# atmega128ictop.net
KiCad netlist of a schematic drawn in EAGLE
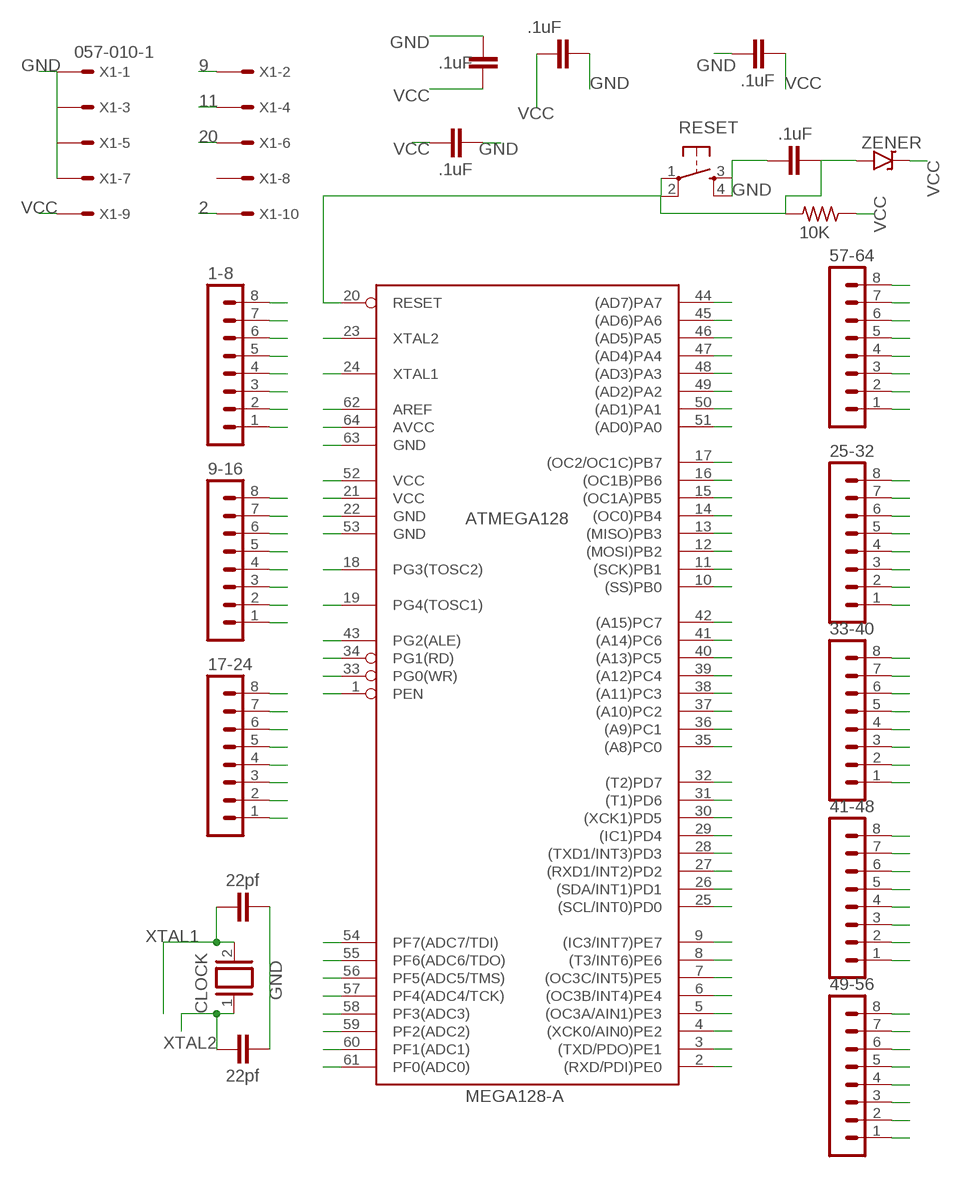
[diagram p0: schematic, sheet 1]

(export (version "E")
  (design (tool "Eeschema 10.0.6"))
  (components
    (comp (ref "1-8")
      (value "MA08-1")
      (footprint "eagle-import:MA08-1")
      (libsource (lib "eagle-import") (part "MA08-1"))
    )
    (comp (ref "9-16")
      (value "MA08-1")
      (footprint "eagle-import:MA08-1")
      (libsource (lib "eagle-import") (part "MA08-1"))
    )
    (comp (ref "17-24")
      (value "MA08-1")
      (footprint "eagle-import:MA08-1")
      (libsource (lib "eagle-import") (part "MA08-1"))
    )
    (comp (ref "25-32")
      (value "MA08-1")
      (footprint "eagle-import:MA08-1")
      (libsource (lib "eagle-import") (part "MA08-1"))
    )
    (comp (ref "33-40")
      (value "MA08-1")
      (footprint "eagle-import:MA08-1")
      (libsource (lib "eagle-import") (part "MA08-1"))
    )
    (comp (ref "41-48")
      (value "MA08-1")
      (footprint "eagle-import:MA08-1")
      (libsource (lib "eagle-import") (part "MA08-1"))
    )
    (comp (ref "49-56")
      (value "MA08-1")
      (footprint "eagle-import:MA08-1")
      (libsource (lib "eagle-import") (part "MA08-1"))
    )
    (comp (ref "57-64")
      (value "MA08-1")
      (footprint "eagle-import:MA08-1")
      (libsource (lib "eagle-import") (part "MA08-1"))
    )
    (comp (ref "ATMEGA128")
      (value "MEGA128-A")
      (footprint "eagle-import:TQFP64")
      (fields (field (name "MPN") "ATMEGA128-16AU"))
      (libsource (lib "eagle-import") (part "MEGA128-A"))
    )
    (comp (ref "C1")
      (value ".1uF")
      (footprint "eagle-import:C5B2.5")
      (libsource (lib "eagle-import") (part "C5/2.5"))
    )
    (comp (ref "C2")
      (value ".1uF")
      (footprint "eagle-import:C5B2.5")
      (libsource (lib "eagle-import") (part "C5/2.5"))
    )
    (comp (ref "C3")
      (value "22pf")
      (footprint "eagle-import:C5B2.5")
      (libsource (lib "eagle-import") (part "C5/2.5"))
    )
    (comp (ref "C4")
      (value "22pf")
      (footprint "eagle-import:C5B2.5")
      (libsource (lib "eagle-import") (part "C5/2.5"))
    )
    (comp (ref "C5")
      (value ".1uF")
      (footprint "eagle-import:C5B2.5")
      (libsource (lib "eagle-import") (part "C5/2.5"))
    )
    (comp (ref "C6")
      (value ".1uF")
      (footprint "eagle-import:C5B2.5")
      (libsource (lib "eagle-import") (part "C5/2.5"))
    )
    (comp (ref "C7")
      (value ".1uF")
      (footprint "eagle-import:C5B2.5")
      (libsource (lib "eagle-import") (part "C5/2.5"))
    )
    (comp (ref "CLOCK")
      (value "XTAL/S")
      (footprint "eagle-import:QS")
      (libsource (lib "eagle-import") (part "XTAL/S"))
    )
    (comp (ref "D1")
      (value "ZENER")
      (footprint "eagle-import:DO35-2")
      (libsource (lib "eagle-import") (part "1N9ZENER2"))
    )
    (comp (ref "R1")
      (value "10K")
      (footprint "eagle-import:0204_5")
      (libsource (lib "eagle-import") (part "R-US_0204/5"))
    )
    (comp (ref "RESET")
      (value "DTS-6")
      (footprint "eagle-import:DTS-6")
      (libsource (lib "eagle-import") (part "DTS-6"))
    )
    (comp (ref "X1")
      (value "057-010-1")
      (footprint "eagle-import:057-010-1")
      (libsource (lib "eagle-import") (part "057-010-1"))
    )
  )
  (nets
    (net (code "1") (name "/1") (class "Default")
      (node (ref "1-8") (pin "1") (pinfunction "1_1") (pintype "passive"))
      (node (ref "ATMEGA128") (pin "1") (pinfunction "PEN_1") (pintype "input"))
    )
    (net (code "2") (name "/2") (class "Default")
      (node (ref "1-8") (pin "2") (pinfunction "2_2") (pintype "passive"))
      (node (ref "ATMEGA128") (pin "2") (pinfunction "(RXD/PDI)PE0_2") (pintype "bidirectional"))
      (node (ref "X1") (pin "10") (pinfunction "S_10") (pintype "passive"))
    )
    (net (code "3") (name "/3") (class "Default")
      (node (ref "1-8") (pin "3") (pinfunction "3_3") (pintype "passive"))
      (node (ref "ATMEGA128") (pin "3") (pinfunction "(TXD/PDO)PE1_3") (pintype "bidirectional"))
    )
    (net (code "4") (name "/4") (class "Default")
      (node (ref "1-8") (pin "4") (pinfunction "4_4") (pintype "passive"))
      (node (ref "ATMEGA128") (pin "4") (pinfunction "(XCK0/AIN0)PE2_4") (pintype "bidirectional"))
    )
    (net (code "5") (name "/5") (class "Default")
      (node (ref "1-8") (pin "5") (pinfunction "5_5") (pintype "passive"))
      (node (ref "ATMEGA128") (pin "5") (pinfunction "(OC3A/AIN1)PE3_5") (pintype "bidirectional"))
    )
    (net (code "6") (name "/6") (class "Default")
      (node (ref "1-8") (pin "6") (pinfunction "6_6") (pintype "passive"))
      (node (ref "ATMEGA128") (pin "6") (pinfunction "(OC3B/INT4)PE4_6") (pintype "bidirectional"))
    )
    (net (code "7") (name "/7") (class "Default")
      (node (ref "1-8") (pin "7") (pinfunction "7_7") (pintype "passive"))
      (node (ref "ATMEGA128") (pin "7") (pinfunction "(OC3C/INT5)PE5_7") (pintype "bidirectional"))
    )
    (net (code "8") (name "/8") (class "Default")
      (node (ref "1-8") (pin "8") (pinfunction "8_8") (pintype "passive"))
      (node (ref "ATMEGA128") (pin "8") (pinfunction "(T3/INT6)PE6_8") (pintype "bidirectional"))
    )
    (net (code "9") (name "/9") (class "Default")
      (node (ref "9-16") (pin "1") (pinfunction "1_1") (pintype "passive"))
      (node (ref "ATMEGA128") (pin "9") (pinfunction "(IC3/INT7)PE7_9") (pintype "bidirectional"))
      (node (ref "X1") (pin "2") (pinfunction "S_2") (pintype "passive"))
    )
    (net (code "10") (name "/10") (class "Default")
      (node (ref "9-16") (pin "2") (pinfunction "2_2") (pintype "passive"))
      (node (ref "ATMEGA128") (pin "10") (pinfunction "(SS)PB0_10") (pintype "bidirectional"))
    )
    (net (code "11") (name "/11") (class "Default")
      (node (ref "9-16") (pin "3") (pinfunction "3_3") (pintype "passive"))
      (node (ref "ATMEGA128") (pin "11") (pinfunction "(SCK)PB1_11") (pintype "bidirectional"))
      (node (ref "X1") (pin "4") (pinfunction "S_4") (pintype "passive"))
    )
    (net (code "12") (name "/12") (class "Default")
      (node (ref "9-16") (pin "4") (pinfunction "4_4") (pintype "passive"))
      (node (ref "ATMEGA128") (pin "12") (pinfunction "(MOSI)PB2_12") (pintype "bidirectional"))
    )
    (net (code "13") (name "/13") (class "Default")
      (node (ref "9-16") (pin "5") (pinfunction "5_5") (pintype "passive"))
      (node (ref "ATMEGA128") (pin "13") (pinfunction "(MISO)PB3_13") (pintype "bidirectional"))
    )
    (net (code "14") (name "/14") (class "Default")
      (node (ref "9-16") (pin "6") (pinfunction "6_6") (pintype "passive"))
      (node (ref "ATMEGA128") (pin "14") (pinfunction "(OC0)PB4_14") (pintype "bidirectional"))
    )
    (net (code "15") (name "/15") (class "Default")
      (node (ref "9-16") (pin "7") (pinfunction "7_7") (pintype "passive"))
      (node (ref "ATMEGA128") (pin "15") (pinfunction "(OC1A)PB5_15") (pintype "bidirectional"))
    )
    (net (code "16") (name "/16") (class "Default")
      (node (ref "9-16") (pin "8") (pinfunction "8_8") (pintype "passive"))
      (node (ref "ATMEGA128") (pin "16") (pinfunction "(OC1B)PB6_16") (pintype "bidirectional"))
    )
    (net (code "17") (name "/17") (class "Default")
      (node (ref "17-24") (pin "1") (pinfunction "1_1") (pintype "passive"))
      (node (ref "ATMEGA128") (pin "17") (pinfunction "(OC2/OC1C)PB7_17") (pintype "bidirectional"))
    )
    (net (code "18") (name "/18") (class "Default")
      (node (ref "17-24") (pin "2") (pinfunction "2_2") (pintype "passive"))
      (node (ref "ATMEGA128") (pin "18") (pinfunction "PG3(TOSC2)_18") (pintype "bidirectional"))
    )
    (net (code "19") (name "/19") (class "Default")
      (node (ref "17-24") (pin "3") (pinfunction "3_3") (pintype "passive"))
      (node (ref "ATMEGA128") (pin "19") (pinfunction "PG4(TOSC1)_19") (pintype "bidirectional"))
    )
    (net (code "20") (name "/20") (class "Default")
      (node (ref "17-24") (pin "4") (pinfunction "4_4") (pintype "passive"))
      (node (ref "ATMEGA128") (pin "20") (pinfunction "RESET_20") (pintype "input"))
      (node (ref "C5") (pin "1") (pinfunction "1_1") (pintype "passive"))
      (node (ref "D1") (pin "A") (pinfunction "A_A") (pintype "passive"))
      (node (ref "R1") (pin "2") (pinfunction "2_2") (pintype "passive"))
      (node (ref "RESET") (pin "1") (pinfunction "1_1") (pintype "passive"))
      (node (ref "RESET") (pin "2") (pinfunction "2_2") (pintype "passive"))
      (node (ref "X1") (pin "6") (pinfunction "S_6") (pintype "passive"))
    )
    (net (code "21") (name "/25") (class "Default")
      (node (ref "25-32") (pin "1") (pinfunction "1_1") (pintype "passive"))
      (node (ref "ATMEGA128") (pin "25") (pinfunction "(SCL/INT0)PD0_25") (pintype "bidirectional"))
    )
    (net (code "22") (name "/26") (class "Default")
      (node (ref "25-32") (pin "2") (pinfunction "2_2") (pintype "passive"))
      (node (ref "ATMEGA128") (pin "26") (pinfunction "(SDA/INT1)PD1_26") (pintype "bidirectional"))
    )
    (net (code "23") (name "/27") (class "Default")
      (node (ref "25-32") (pin "3") (pinfunction "3_3") (pintype "passive"))
      (node (ref "ATMEGA128") (pin "27") (pinfunction "(RXD1/INT2)PD2_27") (pintype "bidirectional"))
    )
    (net (code "24") (name "/28") (class "Default")
      (node (ref "25-32") (pin "4") (pinfunction "4_4") (pintype "passive"))
      (node (ref "ATMEGA128") (pin "28") (pinfunction "(TXD1/INT3)PD3_28") (pintype "bidirectional"))
    )
    (net (code "25") (name "/29") (class "Default")
      (node (ref "25-32") (pin "5") (pinfunction "5_5") (pintype "passive"))
      (node (ref "ATMEGA128") (pin "29") (pinfunction "(IC1)PD4_29") (pintype "bidirectional"))
    )
    (net (code "26") (name "/30") (class "Default")
      (node (ref "25-32") (pin "6") (pinfunction "6_6") (pintype "passive"))
      (node (ref "ATMEGA128") (pin "30") (pinfunction "(XCK1)PD5_30") (pintype "bidirectional"))
    )
    (net (code "27") (name "/31") (class "Default")
      (node (ref "25-32") (pin "7") (pinfunction "7_7") (pintype "passive"))
      (node (ref "ATMEGA128") (pin "31") (pinfunction "(T1)PD6_31") (pintype "bidirectional"))
    )
    (net (code "28") (name "/32") (class "Default")
      (node (ref "25-32") (pin "8") (pinfunction "8_8") (pintype "passive"))
      (node (ref "ATMEGA128") (pin "32") (pinfunction "(T2)PD7_32") (pintype "bidirectional"))
    )
    (net (code "29") (name "/33") (class "Default")
      (node (ref "33-40") (pin "1") (pinfunction "1_1") (pintype "passive"))
      (node (ref "ATMEGA128") (pin "33") (pinfunction "PG0(WR)_33") (pintype "bidirectional"))
    )
    (net (code "30") (name "/34") (class "Default")
      (node (ref "33-40") (pin "2") (pinfunction "2_2") (pintype "passive"))
      (node (ref "ATMEGA128") (pin "34") (pinfunction "PG1(RD)_34") (pintype "bidirectional"))
    )
    (net (code "31") (name "/35") (class "Default")
      (node (ref "33-40") (pin "3") (pinfunction "3_3") (pintype "passive"))
      (node (ref "ATMEGA128") (pin "35") (pinfunction "(A8)PC0_35") (pintype "output"))
    )
    (net (code "32") (name "/36") (class "Default")
      (node (ref "33-40") (pin "4") (pinfunction "4_4") (pintype "passive"))
      (node (ref "ATMEGA128") (pin "36") (pinfunction "(A9)PC1_36") (pintype "output"))
    )
    (net (code "33") (name "/37") (class "Default")
      (node (ref "33-40") (pin "5") (pinfunction "5_5") (pintype "passive"))
      (node (ref "ATMEGA128") (pin "37") (pinfunction "(A10)PC2_37") (pintype "output"))
    )
    (net (code "34") (name "/38") (class "Default")
      (node (ref "33-40") (pin "6") (pinfunction "6_6") (pintype "passive"))
      (node (ref "ATMEGA128") (pin "38") (pinfunction "(A11)PC3_38") (pintype "output"))
    )
    (net (code "35") (name "/39") (class "Default")
      (node (ref "33-40") (pin "7") (pinfunction "7_7") (pintype "passive"))
      (node (ref "ATMEGA128") (pin "39") (pinfunction "(A12)PC4_39") (pintype "output"))
    )
    (net (code "36") (name "/40") (class "Default")
      (node (ref "33-40") (pin "8") (pinfunction "8_8") (pintype "passive"))
      (node (ref "ATMEGA128") (pin "40") (pinfunction "(A13)PC5_40") (pintype "output"))
    )
    (net (code "37") (name "/41") (class "Default")
      (node (ref "41-48") (pin "1") (pinfunction "1_1") (pintype "passive"))
      (node (ref "ATMEGA128") (pin "41") (pinfunction "(A14)PC6_41") (pintype "output"))
    )
    (net (code "38") (name "/42") (class "Default")
      (node (ref "41-48") (pin "2") (pinfunction "2_2") (pintype "passive"))
      (node (ref "ATMEGA128") (pin "42") (pinfunction "(A15)PC7_42") (pintype "output"))
    )
    (net (code "39") (name "/43") (class "Default")
      (node (ref "41-48") (pin "3") (pinfunction "3_3") (pintype "passive"))
      (node (ref "ATMEGA128") (pin "43") (pinfunction "PG2(ALE)_43") (pintype "bidirectional"))
    )
    (net (code "40") (name "/44") (class "Default")
      (node (ref "41-48") (pin "4") (pinfunction "4_4") (pintype "passive"))
      (node (ref "ATMEGA128") (pin "44") (pinfunction "(AD7)PA7_44") (pintype "bidirectional"))
    )
    (net (code "41") (name "/45") (class "Default")
      (node (ref "41-48") (pin "5") (pinfunction "5_5") (pintype "passive"))
      (node (ref "ATMEGA128") (pin "45") (pinfunction "(AD6)PA6_45") (pintype "bidirectional"))
    )
    (net (code "42") (name "/46") (class "Default")
      (node (ref "41-48") (pin "6") (pinfunction "6_6") (pintype "passive"))
      (node (ref "ATMEGA128") (pin "46") (pinfunction "(AD5)PA5_46") (pintype "bidirectional"))
    )
    (net (code "43") (name "/47") (class "Default")
      (node (ref "41-48") (pin "7") (pinfunction "7_7") (pintype "passive"))
      (node (ref "ATMEGA128") (pin "47") (pinfunction "(AD4)PA4_47") (pintype "bidirectional"))
    )
    (net (code "44") (name "/48") (class "Default")
      (node (ref "41-48") (pin "8") (pinfunction "8_8") (pintype "passive"))
      (node (ref "ATMEGA128") (pin "48") (pinfunction "(AD3)PA3_48") (pintype "bidirectional"))
    )
    (net (code "45") (name "/49") (class "Default")
      (node (ref "49-56") (pin "1") (pinfunction "1_1") (pintype "passive"))
      (node (ref "ATMEGA128") (pin "49") (pinfunction "(AD2)PA2_49") (pintype "bidirectional"))
    )
    (net (code "46") (name "/50") (class "Default")
      (node (ref "49-56") (pin "2") (pinfunction "2_2") (pintype "passive"))
      (node (ref "ATMEGA128") (pin "50") (pinfunction "(AD1)PA1_50") (pintype "bidirectional"))
    )
    (net (code "47") (name "/51") (class "Default")
      (node (ref "49-56") (pin "3") (pinfunction "3_3") (pintype "passive"))
      (node (ref "ATMEGA128") (pin "51") (pinfunction "(AD0)PA0_51") (pintype "bidirectional"))
    )
    (net (code "48") (name "/54") (class "Default")
      (node (ref "49-56") (pin "6") (pinfunction "6_6") (pintype "passive"))
      (node (ref "ATMEGA128") (pin "54") (pinfunction "PF7(ADC7/TDI)_54") (pintype "input"))
    )
    (net (code "49") (name "/55") (class "Default")
      (node (ref "49-56") (pin "7") (pinfunction "7_7") (pintype "passive"))
      (node (ref "ATMEGA128") (pin "55") (pinfunction "PF6(ADC6/TDO)_55") (pintype "input"))
    )
    (net (code "50") (name "/56") (class "Default")
      (node (ref "49-56") (pin "8") (pinfunction "8_8") (pintype "passive"))
      (node (ref "ATMEGA128") (pin "56") (pinfunction "PF5(ADC5/TMS)_56") (pintype "input"))
    )
    (net (code "51") (name "/57") (class "Default")
      (node (ref "57-64") (pin "1") (pinfunction "1_1") (pintype "passive"))
      (node (ref "ATMEGA128") (pin "57") (pinfunction "PF4(ADC4/TCK)_57") (pintype "input"))
    )
    (net (code "52") (name "/58") (class "Default")
      (node (ref "57-64") (pin "2") (pinfunction "2_2") (pintype "passive"))
      (node (ref "ATMEGA128") (pin "58") (pinfunction "PF3(ADC3)_58") (pintype "input"))
    )
    (net (code "53") (name "/59") (class "Default")
      (node (ref "57-64") (pin "3") (pinfunction "3_3") (pintype "passive"))
      (node (ref "ATMEGA128") (pin "59") (pinfunction "PF2(ADC2)_59") (pintype "input"))
    )
    (net (code "54") (name "/60") (class "Default")
      (node (ref "57-64") (pin "4") (pinfunction "4_4") (pintype "passive"))
      (node (ref "ATMEGA128") (pin "60") (pinfunction "PF1(ADC1)_60") (pintype "input"))
    )
    (net (code "55") (name "/61") (class "Default")
      (node (ref "57-64") (pin "5") (pinfunction "5_5") (pintype "passive"))
      (node (ref "ATMEGA128") (pin "61") (pinfunction "PF0(ADC0)_61") (pintype "input"))
    )
    (net (code "56") (name "/GND") (class "Default")
      (node (ref "17-24") (pin "6") (pinfunction "6_6") (pintype "passive"))
      (node (ref "49-56") (pin "5") (pinfunction "5_5") (pintype "passive"))
      (node (ref "57-64") (pin "7") (pinfunction "7_7") (pintype "passive"))
      (node (ref "ATMEGA128") (pin "22") (pinfunction "GND_22") (pintype "power_in"))
      (node (ref "ATMEGA128") (pin "53") (pinfunction "GND_53") (pintype "power_in"))
      (node (ref "ATMEGA128") (pin "63") (pinfunction "GND_63") (pintype "power_in"))
      (node (ref "C1") (pin "1") (pinfunction "1_1") (pintype "passive"))
      (node (ref "C2") (pin "2") (pinfunction "2_2") (pintype "passive"))
      (node (ref "C3") (pin "2") (pinfunction "2_2") (pintype "passive"))
      (node (ref "C4") (pin "2") (pinfunction "2_2") (pintype "passive"))
      (node (ref "C5") (pin "2") (pinfunction "2_2") (pintype "passive"))
      (node (ref "C6") (pin "2") (pinfunction "2_2") (pintype "passive"))
      (node (ref "C7") (pin "2") (pinfunction "2_2") (pintype "passive"))
      (node (ref "RESET") (pin "3") (pinfunction "3_3") (pintype "passive"))
      (node (ref "RESET") (pin "4") (pinfunction "4_4") (pintype "passive"))
      (node (ref "X1") (pin "1") (pinfunction "S_1") (pintype "passive"))
      (node (ref "X1") (pin "3") (pinfunction "S_3") (pintype "passive"))
      (node (ref "X1") (pin "5") (pinfunction "S_5") (pintype "passive"))
      (node (ref "X1") (pin "7") (pinfunction "S_7") (pintype "passive"))
    )
    (net (code "57") (name "/VCC") (class "Default")
      (node (ref "17-24") (pin "5") (pinfunction "5_5") (pintype "passive"))
      (node (ref "49-56") (pin "4") (pinfunction "4_4") (pintype "passive"))
      (node (ref "57-64") (pin "8") (pinfunction "8_8") (pintype "passive"))
      (node (ref "ATMEGA128") (pin "21") (pinfunction "VCC_21") (pintype "power_in"))
      (node (ref "ATMEGA128") (pin "52") (pinfunction "VCC_52") (pintype "power_in"))
      (node (ref "ATMEGA128") (pin "62") (pinfunction "AREF_62") (pintype "passive"))
      (node (ref "ATMEGA128") (pin "64") (pinfunction "AVCC_64") (pintype "power_in"))
      (node (ref "C1") (pin "2") (pinfunction "2_2") (pintype "passive"))
      (node (ref "C2") (pin "1") (pinfunction "1_1") (pintype "passive"))
      (node (ref "C6") (pin "1") (pinfunction "1_1") (pintype "passive"))
      (node (ref "C7") (pin "1") (pinfunction "1_1") (pintype "passive"))
      (node (ref "D1") (pin "C") (pinfunction "C_C") (pintype "passive"))
      (node (ref "R1") (pin "1") (pinfunction "1_1") (pintype "passive"))
      (node (ref "X1") (pin "9") (pinfunction "S_9") (pintype "passive"))
    )
    (net (code "58") (name "/XTAL1") (class "Default")
      (node (ref "17-24") (pin "8") (pinfunction "8_8") (pintype "passive"))
      (node (ref "ATMEGA128") (pin "24") (pinfunction "XTAL1_24") (pintype "bidirectional"))
      (node (ref "C3") (pin "1") (pinfunction "1_1") (pintype "passive"))
      (node (ref "CLOCK") (pin "2") (pinfunction "2_2") (pintype "passive"))
    )
    (net (code "59") (name "/XTAL2") (class "Default")
      (node (ref "17-24") (pin "7") (pinfunction "7_7") (pintype "passive"))
      (node (ref "ATMEGA128") (pin "23") (pinfunction "XTAL2_23") (pintype "bidirectional"))
      (node (ref "C4") (pin "1") (pinfunction "1_1") (pintype "passive"))
      (node (ref "CLOCK") (pin "1") (pinfunction "1_1") (pintype "passive"))
    )
    (net (code "60") (name "unconnected-(57-64-Pad6)") (class "Default")
      (node (ref "57-64") (pin "6") (pinfunction "6_6") (pintype "passive"))
    )
    (net (code "61") (name "unconnected-(X1I-S-Pad8)") (class "Default")
      (node (ref "X1") (pin "8") (pinfunction "S_8") (pintype "passive"))
    )
  )
)
